# 6_QSPI.net
KiCad netlist of a schematic drawn in Altium Designer
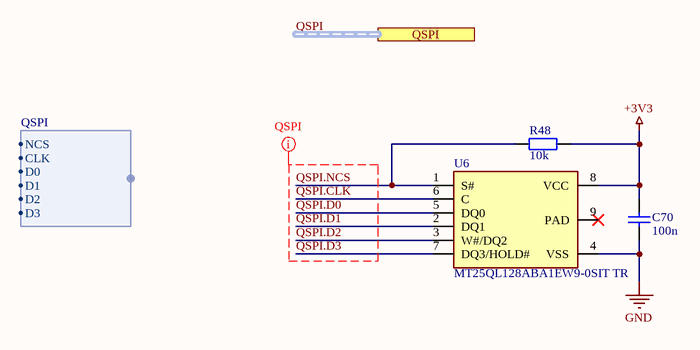
[diagram p0: [6] QSPI.SchDoc]

(export (version "E")
  (design (tool "Eeschema 10.0.6"))
  (components
    (comp (ref "C70")
      (value "100n")
      (footprint "STguitar:Capacitor 0603")
      (description "Multilayer Ceramic Capacitors MLCC - SMD/SMT 0603 16VDC 0.1uF 10% X7R")
      (fields
        (field (name "MANUFACTURER PART NUMBER") "EMK107B7104KA-T")
        (field (name "MANUFACTURER") "Taiyo Yuden")
      )
      (libsource (lib "STguitar") (part "Capacitor 100n 10% 0603 EMK107B7104KA-T"))
    )
    (comp (ref "R48")
      (value "10k")
      (footprint "STguitar:Resistor 0603")
      (description "Thin Film Resistors - SMD 10K ohm 1% 1/10W")
      (fields
        (field (name "MANUFACTURER PART NUMBER") "RT0603FRE0710KL")
        (field (name "MANUFACTURER") "Yageo")
      )
      (libsource (lib "STguitar") (part "Resistor 10k 1% 0603 RT0603FRE0710KL"))
    )
    (comp (ref "U6")
      (value "MT25QL128ABA1EW9-0SIT TR")
      (footprint "STguitar:WDFN8")
      (description "NOR Flash SPI FLASH NOR SLC 32MX4 WPDFN")
      (fields (field (name "MANUFACTURER") "Micron"))
      (libsource (lib "STguitar") (part "IC NOR Flash SPI FLASH NOR SLC 32MX4 WPDFN MT25QL128ABA1EW9-0SIT TR"))
    )
  )
  (nets
    (net (code "2") (name "+3V3") (class "Default")
      (node (ref "C70") (pin "2") (pinfunction "2_2") (pintype "passive"))
      (node (ref "R48") (pin "2") (pinfunction "2_2") (pintype "passive"))
      (node (ref "U6") (pin "8") (pinfunction "VCC_8") (pintype "passive"))
    )
    (net (code "3") (name "/QSPI.CLK") (class "Default")
      (node (ref "U6") (pin "6") (pinfunction "C_6") (pintype "passive"))
    )
    (net (code "4") (name "/QSPI.D0") (class "Default")
      (node (ref "U6") (pin "5") (pinfunction "DQ0_5") (pintype "passive"))
    )
    (net (code "5") (name "/QSPI.D1") (class "Default")
      (node (ref "U6") (pin "2") (pinfunction "DQ1_2") (pintype "passive"))
    )
    (net (code "6") (name "/QSPI.D2") (class "Default")
      (node (ref "U6") (pin "3") (pinfunction "W#/DQ2_3") (pintype "passive"))
    )
    (net (code "7") (name "/QSPI.D3") (class "Default")
      (node (ref "U6") (pin "7") (pinfunction "DQ3/HOLD#_7") (pintype "passive"))
    )
    (net (code "8") (name "/QSPI.NCS") (class "Default")
      (node (ref "R48") (pin "1") (pinfunction "1_1") (pintype "passive"))
      (node (ref "U6") (pin "1") (pinfunction "S#_1") (pintype "passive"))
    )
    (net (code "10") (name "GND") (class "Default")
      (node (ref "C70") (pin "1") (pinfunction "1_1") (pintype "passive"))
      (node (ref "U6") (pin "4") (pinfunction "VSS_4") (pintype "passive"))
    )
    (net (code "11") (name "unconnected-(U6-PAD-Pad9)") (class "Default")
      (node (ref "U6") (pin "9") (pinfunction "PAD_9") (pintype "passive+no_connect"))
    )
  )
)
